# Sheet1.net
KiCad netlist of a schematic drawn in Altium Designer
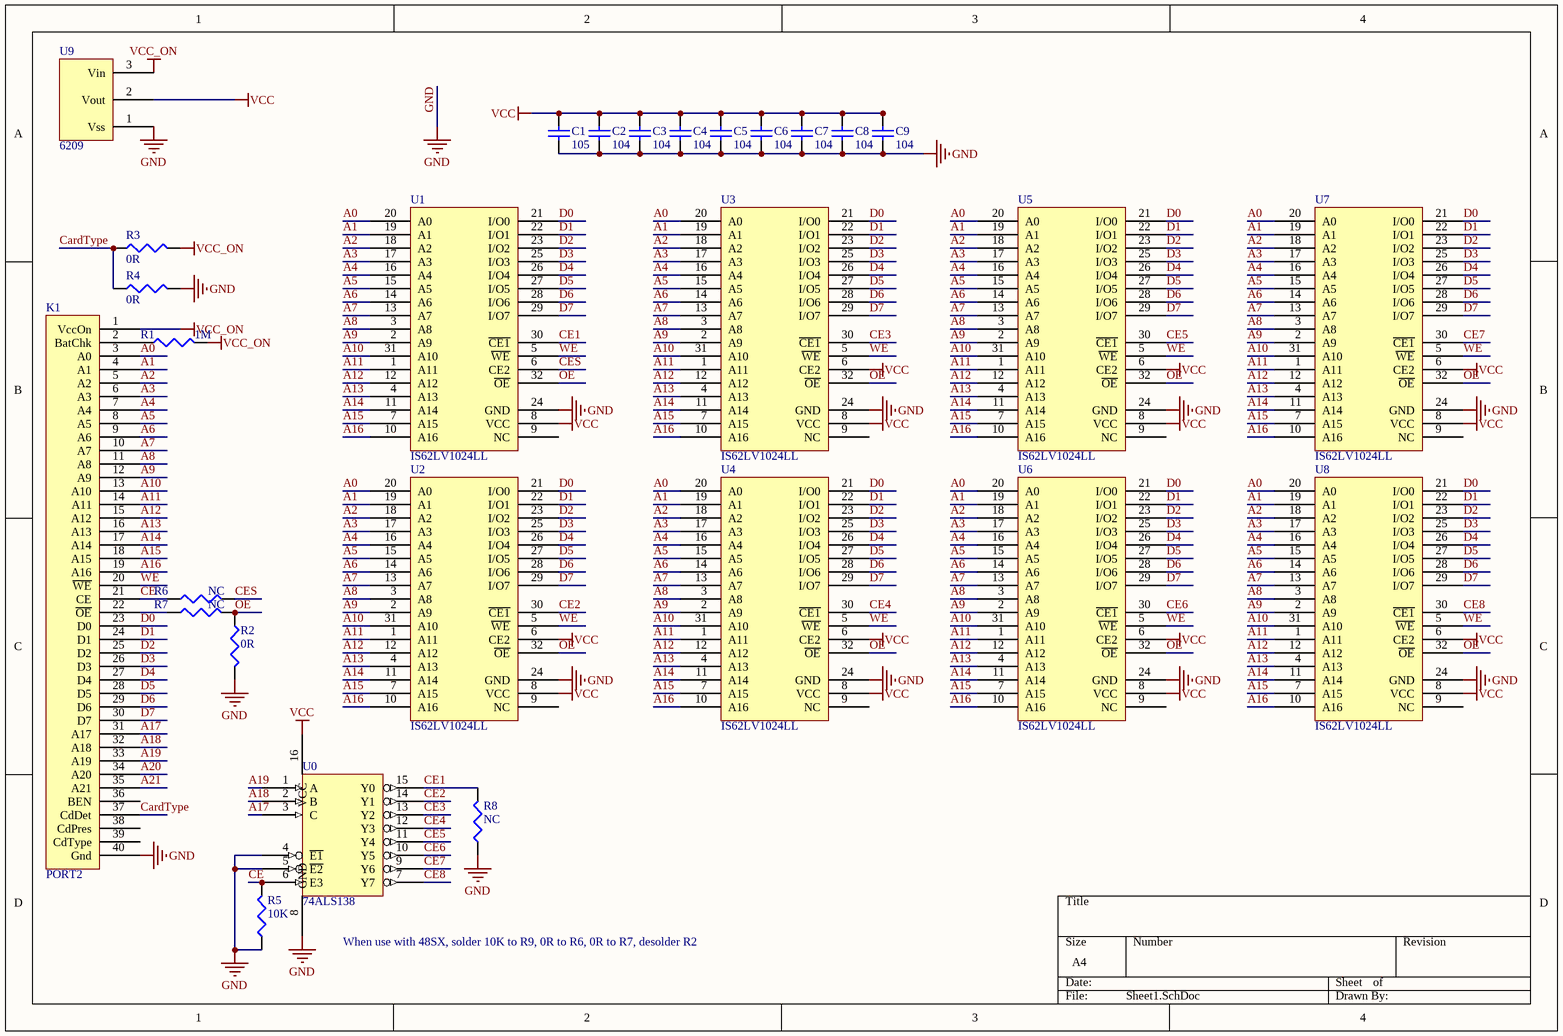
[diagram p0: Sheet1.SchDoc]

(export (version "E")
  (design (tool "Eeschema 10.0.6"))
  (components
    (comp (ref "C1")
      (value "105")
      (footprint "1608[0603]")
      (description "Capacitor (Semiconductor SIM Model)")
      (fields (field (name "PUBLISHER") "Altium Limited"))
      (libsource (lib "Miscellaneous Devices") (part "Cap Semi"))
    )
    (comp (ref "C2")
      (value "104")
      (footprint "1608[0603]")
      (description "Capacitor (Semiconductor SIM Model)")
      (fields (field (name "PUBLISHER") "Altium Limited"))
      (libsource (lib "Miscellaneous Devices") (part "Cap Semi"))
    )
    (comp (ref "C3")
      (value "104")
      (footprint "1608[0603]")
      (description "Capacitor (Semiconductor SIM Model)")
      (fields (field (name "PUBLISHER") "Altium Limited"))
      (libsource (lib "Miscellaneous Devices") (part "Cap Semi"))
    )
    (comp (ref "C4")
      (value "104")
      (footprint "1608[0603]")
      (description "Capacitor (Semiconductor SIM Model)")
      (fields (field (name "PUBLISHER") "Altium Limited"))
      (libsource (lib "Miscellaneous Devices") (part "Cap Semi"))
    )
    (comp (ref "C5")
      (value "104")
      (footprint "1608[0603]")
      (description "Capacitor (Semiconductor SIM Model)")
      (fields (field (name "PUBLISHER") "Altium Limited"))
      (libsource (lib "Miscellaneous Devices") (part "Cap Semi"))
    )
    (comp (ref "C6")
      (value "104")
      (footprint "1608[0603]")
      (description "Capacitor (Semiconductor SIM Model)")
      (fields (field (name "PUBLISHER") "Altium Limited"))
      (libsource (lib "Miscellaneous Devices") (part "Cap Semi"))
    )
    (comp (ref "C7")
      (value "104")
      (footprint "1608[0603]")
      (description "Capacitor (Semiconductor SIM Model)")
      (fields (field (name "PUBLISHER") "Altium Limited"))
      (libsource (lib "Miscellaneous Devices") (part "Cap Semi"))
    )
    (comp (ref "C8")
      (value "104")
      (footprint "1608[0603]")
      (description "Capacitor (Semiconductor SIM Model)")
      (fields (field (name "PUBLISHER") "Altium Limited"))
      (libsource (lib "Miscellaneous Devices") (part "Cap Semi"))
    )
    (comp (ref "C9")
      (value "104")
      (footprint "1608[0603]")
      (description "Capacitor (Semiconductor SIM Model)")
      (fields (field (name "PUBLISHER") "Altium Limited"))
      (libsource (lib "Miscellaneous Devices") (part "Cap Semi"))
    )
    (comp (ref "K1") (value "PORT2") (footprint "SOP80") (libsource (lib "Schlib1") (part "PORT2")))
    (comp (ref "R1")
      (value "1M")
      (footprint "J1-0603")
      (description "Resistor")
      (fields (field (name "PUBLISHER") "Altium Limited"))
      (libsource (lib "Miscellaneous Devices") (part "Res3"))
    )
    (comp (ref "R2")
      (value "0R")
      (footprint "J1-0603")
      (description "Resistor")
      (fields (field (name "PUBLISHER") "Altium Limited"))
      (libsource (lib "Miscellaneous Devices") (part "Res3"))
    )
    (comp (ref "R3")
      (value "0R")
      (footprint "J1-0603")
      (description "Resistor")
      (fields (field (name "PUBLISHER") "Altium Limited"))
      (libsource (lib "Miscellaneous Devices") (part "Res3"))
    )
    (comp (ref "R4")
      (value "0R")
      (footprint "J1-0603")
      (description "Resistor")
      (fields (field (name "PUBLISHER") "Altium Limited"))
      (libsource (lib "Miscellaneous Devices") (part "Res3"))
    )
    (comp (ref "R5")
      (value "10K")
      (footprint "J1-0603")
      (description "Resistor")
      (fields (field (name "PUBLISHER") "Altium Limited"))
      (libsource (lib "Miscellaneous Devices") (part "Res3"))
    )
    (comp (ref "R6")
      (value "NC")
      (footprint "J1-0603")
      (description "Resistor")
      (fields (field (name "PUBLISHER") "Altium Limited"))
      (libsource (lib "Miscellaneous Devices") (part "Res3"))
    )
    (comp (ref "R7")
      (value "NC")
      (footprint "J1-0603")
      (description "Resistor")
      (fields (field (name "PUBLISHER") "Altium Limited"))
      (libsource (lib "Miscellaneous Devices") (part "Res3"))
    )
    (comp (ref "R8")
      (value "NC")
      (footprint "J1-0603")
      (description "Resistor")
      (fields (field (name "PUBLISHER") "Altium Limited"))
      (libsource (lib "Miscellaneous Devices") (part "Res3"))
    )
    (comp (ref "U0") (value "74ALS138") (footprint "SO-16") (libsource (lib "TTL74系列IC") (part "74ALS138")))
    (comp (ref "U1")
      (value "IS62LV1024LL")
      (footprint "TSOP32")
      (libsource (lib "Schlib1") (part "IS62LV1024LL"))
    )
    (comp (ref "U2")
      (value "IS62LV1024LL")
      (footprint "TSOP32")
      (libsource (lib "Schlib1") (part "IS62LV1024LL"))
    )
    (comp (ref "U3")
      (value "IS62LV1024LL")
      (footprint "TSOP32")
      (libsource (lib "Schlib1") (part "IS62LV1024LL"))
    )
    (comp (ref "U4")
      (value "IS62LV1024LL")
      (footprint "TSOP32")
      (libsource (lib "Schlib1") (part "IS62LV1024LL"))
    )
    (comp (ref "U5")
      (value "IS62LV1024LL")
      (footprint "TSOP32")
      (libsource (lib "Schlib1") (part "IS62LV1024LL"))
    )
    (comp (ref "U6")
      (value "IS62LV1024LL")
      (footprint "TSOP32")
      (libsource (lib "Schlib1") (part "IS62LV1024LL"))
    )
    (comp (ref "U7")
      (value "IS62LV1024LL")
      (footprint "TSOP32")
      (libsource (lib "Schlib1") (part "IS62LV1024LL"))
    )
    (comp (ref "U8")
      (value "IS62LV1024LL")
      (footprint "TSOP32")
      (libsource (lib "Schlib1") (part "IS62LV1024LL"))
    )
    (comp (ref "U9") (value "6209") (footprint "SOT-23") (libsource (lib "Schlib1") (part "6209")))
  )
  (nets
    (net (code "1") (name "/A0") (class "Default")
      (node (ref "K1") (pin "3") (pinfunction "A0_3") (pintype "passive"))
      (node (ref "U1") (pin "20") (pinfunction "A0_20") (pintype "passive"))
      (node (ref "U2") (pin "20") (pinfunction "A0_20") (pintype "passive"))
      (node (ref "U3") (pin "20") (pinfunction "A0_20") (pintype "passive"))
      (node (ref "U4") (pin "20") (pinfunction "A0_20") (pintype "passive"))
      (node (ref "U5") (pin "20") (pinfunction "A0_20") (pintype "passive"))
      (node (ref "U6") (pin "20") (pinfunction "A0_20") (pintype "passive"))
      (node (ref "U7") (pin "20") (pinfunction "A0_20") (pintype "passive"))
      (node (ref "U8") (pin "20") (pinfunction "A0_20") (pintype "passive"))
    )
    (net (code "2") (name "/A1") (class "Default")
      (node (ref "K1") (pin "4") (pinfunction "A1_4") (pintype "passive"))
      (node (ref "U1") (pin "19") (pinfunction "A1_19") (pintype "passive"))
      (node (ref "U2") (pin "19") (pinfunction "A1_19") (pintype "passive"))
      (node (ref "U3") (pin "19") (pinfunction "A1_19") (pintype "passive"))
      (node (ref "U4") (pin "19") (pinfunction "A1_19") (pintype "passive"))
      (node (ref "U5") (pin "19") (pinfunction "A1_19") (pintype "passive"))
      (node (ref "U6") (pin "19") (pinfunction "A1_19") (pintype "passive"))
      (node (ref "U7") (pin "19") (pinfunction "A1_19") (pintype "passive"))
      (node (ref "U8") (pin "19") (pinfunction "A1_19") (pintype "passive"))
    )
    (net (code "3") (name "/A2") (class "Default")
      (node (ref "K1") (pin "5") (pinfunction "A2_5") (pintype "passive"))
      (node (ref "U1") (pin "18") (pinfunction "A2_18") (pintype "passive"))
      (node (ref "U2") (pin "18") (pinfunction "A2_18") (pintype "passive"))
      (node (ref "U3") (pin "18") (pinfunction "A2_18") (pintype "passive"))
      (node (ref "U4") (pin "18") (pinfunction "A2_18") (pintype "passive"))
      (node (ref "U5") (pin "18") (pinfunction "A2_18") (pintype "passive"))
      (node (ref "U6") (pin "18") (pinfunction "A2_18") (pintype "passive"))
      (node (ref "U7") (pin "18") (pinfunction "A2_18") (pintype "passive"))
      (node (ref "U8") (pin "18") (pinfunction "A2_18") (pintype "passive"))
    )
    (net (code "4") (name "/A3") (class "Default")
      (node (ref "K1") (pin "6") (pinfunction "A3_6") (pintype "passive"))
      (node (ref "U1") (pin "17") (pinfunction "A3_17") (pintype "passive"))
      (node (ref "U2") (pin "17") (pinfunction "A3_17") (pintype "passive"))
      (node (ref "U3") (pin "17") (pinfunction "A3_17") (pintype "passive"))
      (node (ref "U4") (pin "17") (pinfunction "A3_17") (pintype "passive"))
      (node (ref "U5") (pin "17") (pinfunction "A3_17") (pintype "passive"))
      (node (ref "U6") (pin "17") (pinfunction "A3_17") (pintype "passive"))
      (node (ref "U7") (pin "17") (pinfunction "A3_17") (pintype "passive"))
      (node (ref "U8") (pin "17") (pinfunction "A3_17") (pintype "passive"))
    )
    (net (code "5") (name "/A4") (class "Default")
      (node (ref "K1") (pin "7") (pinfunction "A4_7") (pintype "passive"))
      (node (ref "U1") (pin "16") (pinfunction "A4_16") (pintype "passive"))
      (node (ref "U2") (pin "16") (pinfunction "A4_16") (pintype "passive"))
      (node (ref "U3") (pin "16") (pinfunction "A4_16") (pintype "passive"))
      (node (ref "U4") (pin "16") (pinfunction "A4_16") (pintype "passive"))
      (node (ref "U5") (pin "16") (pinfunction "A4_16") (pintype "passive"))
      (node (ref "U6") (pin "16") (pinfunction "A4_16") (pintype "passive"))
      (node (ref "U7") (pin "16") (pinfunction "A4_16") (pintype "passive"))
      (node (ref "U8") (pin "16") (pinfunction "A4_16") (pintype "passive"))
    )
    (net (code "6") (name "/A5") (class "Default")
      (node (ref "K1") (pin "8") (pinfunction "A5_8") (pintype "passive"))
      (node (ref "U1") (pin "15") (pinfunction "A5_15") (pintype "passive"))
      (node (ref "U2") (pin "15") (pinfunction "A5_15") (pintype "passive"))
      (node (ref "U3") (pin "15") (pinfunction "A5_15") (pintype "passive"))
      (node (ref "U4") (pin "15") (pinfunction "A5_15") (pintype "passive"))
      (node (ref "U5") (pin "15") (pinfunction "A5_15") (pintype "passive"))
      (node (ref "U6") (pin "15") (pinfunction "A5_15") (pintype "passive"))
      (node (ref "U7") (pin "15") (pinfunction "A5_15") (pintype "passive"))
      (node (ref "U8") (pin "15") (pinfunction "A5_15") (pintype "passive"))
    )
    (net (code "7") (name "/A6") (class "Default")
      (node (ref "K1") (pin "9") (pinfunction "A6_9") (pintype "passive"))
      (node (ref "U1") (pin "14") (pinfunction "A6_14") (pintype "passive"))
      (node (ref "U2") (pin "14") (pinfunction "A6_14") (pintype "passive"))
      (node (ref "U3") (pin "14") (pinfunction "A6_14") (pintype "passive"))
      (node (ref "U4") (pin "14") (pinfunction "A6_14") (pintype "passive"))
      (node (ref "U5") (pin "14") (pinfunction "A6_14") (pintype "passive"))
      (node (ref "U6") (pin "14") (pinfunction "A6_14") (pintype "passive"))
      (node (ref "U7") (pin "14") (pinfunction "A6_14") (pintype "passive"))
      (node (ref "U8") (pin "14") (pinfunction "A6_14") (pintype "passive"))
    )
    (net (code "8") (name "/A7") (class "Default")
      (node (ref "K1") (pin "10") (pinfunction "A7_10") (pintype "passive"))
      (node (ref "U1") (pin "13") (pinfunction "A7_13") (pintype "passive"))
      (node (ref "U2") (pin "13") (pinfunction "A7_13") (pintype "passive"))
      (node (ref "U3") (pin "13") (pinfunction "A7_13") (pintype "passive"))
      (node (ref "U4") (pin "13") (pinfunction "A7_13") (pintype "passive"))
      (node (ref "U5") (pin "13") (pinfunction "A7_13") (pintype "passive"))
      (node (ref "U6") (pin "13") (pinfunction "A7_13") (pintype "passive"))
      (node (ref "U7") (pin "13") (pinfunction "A7_13") (pintype "passive"))
      (node (ref "U8") (pin "13") (pinfunction "A7_13") (pintype "passive"))
    )
    (net (code "9") (name "/A8") (class "Default")
      (node (ref "K1") (pin "11") (pinfunction "A8_11") (pintype "passive"))
      (node (ref "U1") (pin "3") (pinfunction "A8_3") (pintype "passive"))
      (node (ref "U2") (pin "3") (pinfunction "A8_3") (pintype "passive"))
      (node (ref "U3") (pin "3") (pinfunction "A8_3") (pintype "passive"))
      (node (ref "U4") (pin "3") (pinfunction "A8_3") (pintype "passive"))
      (node (ref "U5") (pin "3") (pinfunction "A8_3") (pintype "passive"))
      (node (ref "U6") (pin "3") (pinfunction "A8_3") (pintype "passive"))
      (node (ref "U7") (pin "3") (pinfunction "A8_3") (pintype "passive"))
      (node (ref "U8") (pin "3") (pinfunction "A8_3") (pintype "passive"))
    )
    (net (code "10") (name "/A9") (class "Default")
      (node (ref "K1") (pin "12") (pinfunction "A9_12") (pintype "passive"))
      (node (ref "U1") (pin "2") (pinfunction "A9_2") (pintype "passive"))
      (node (ref "U2") (pin "2") (pinfunction "A9_2") (pintype "passive"))
      (node (ref "U3") (pin "2") (pinfunction "A9_2") (pintype "passive"))
      (node (ref "U4") (pin "2") (pinfunction "A9_2") (pintype "passive"))
      (node (ref "U5") (pin "2") (pinfunction "A9_2") (pintype "passive"))
      (node (ref "U6") (pin "2") (pinfunction "A9_2") (pintype "passive"))
      (node (ref "U7") (pin "2") (pinfunction "A9_2") (pintype "passive"))
      (node (ref "U8") (pin "2") (pinfunction "A9_2") (pintype "passive"))
    )
    (net (code "11") (name "/A10") (class "Default")
      (node (ref "K1") (pin "13") (pinfunction "A10_13") (pintype "passive"))
      (node (ref "U1") (pin "31") (pinfunction "A10_31") (pintype "passive"))
      (node (ref "U2") (pin "31") (pinfunction "A10_31") (pintype "passive"))
      (node (ref "U3") (pin "31") (pinfunction "A10_31") (pintype "passive"))
      (node (ref "U4") (pin "31") (pinfunction "A10_31") (pintype "passive"))
      (node (ref "U5") (pin "31") (pinfunction "A10_31") (pintype "passive"))
      (node (ref "U6") (pin "31") (pinfunction "A10_31") (pintype "passive"))
      (node (ref "U7") (pin "31") (pinfunction "A10_31") (pintype "passive"))
      (node (ref "U8") (pin "31") (pinfunction "A10_31") (pintype "passive"))
    )
    (net (code "12") (name "/A11") (class "Default")
      (node (ref "K1") (pin "14") (pinfunction "A11_14") (pintype "passive"))
      (node (ref "U1") (pin "1") (pinfunction "A11_1") (pintype "passive"))
      (node (ref "U2") (pin "1") (pinfunction "A11_1") (pintype "passive"))
      (node (ref "U3") (pin "1") (pinfunction "A11_1") (pintype "passive"))
      (node (ref "U4") (pin "1") (pinfunction "A11_1") (pintype "passive"))
      (node (ref "U5") (pin "1") (pinfunction "A11_1") (pintype "passive"))
      (node (ref "U6") (pin "1") (pinfunction "A11_1") (pintype "passive"))
      (node (ref "U7") (pin "1") (pinfunction "A11_1") (pintype "passive"))
      (node (ref "U8") (pin "1") (pinfunction "A11_1") (pintype "passive"))
    )
    (net (code "13") (name "/A12") (class "Default")
      (node (ref "K1") (pin "15") (pinfunction "A12_15") (pintype "passive"))
      (node (ref "U1") (pin "12") (pinfunction "A12_12") (pintype "passive"))
      (node (ref "U2") (pin "12") (pinfunction "A12_12") (pintype "passive"))
      (node (ref "U3") (pin "12") (pinfunction "A12_12") (pintype "passive"))
      (node (ref "U4") (pin "12") (pinfunction "A12_12") (pintype "passive"))
      (node (ref "U5") (pin "12") (pinfunction "A12_12") (pintype "passive"))
      (node (ref "U6") (pin "12") (pinfunction "A12_12") (pintype "passive"))
      (node (ref "U7") (pin "12") (pinfunction "A12_12") (pintype "passive"))
      (node (ref "U8") (pin "12") (pinfunction "A12_12") (pintype "passive"))
    )
    (net (code "14") (name "/A13") (class "Default")
      (node (ref "K1") (pin "16") (pinfunction "A13_16") (pintype "passive"))
      (node (ref "U1") (pin "4") (pinfunction "A13_4") (pintype "passive"))
      (node (ref "U2") (pin "4") (pinfunction "A13_4") (pintype "passive"))
      (node (ref "U3") (pin "4") (pinfunction "A13_4") (pintype "passive"))
      (node (ref "U4") (pin "4") (pinfunction "A13_4") (pintype "passive"))
      (node (ref "U5") (pin "4") (pinfunction "A13_4") (pintype "passive"))
      (node (ref "U6") (pin "4") (pinfunction "A13_4") (pintype "passive"))
      (node (ref "U7") (pin "4") (pinfunction "A13_4") (pintype "passive"))
      (node (ref "U8") (pin "4") (pinfunction "A13_4") (pintype "passive"))
    )
    (net (code "15") (name "/A14") (class "Default")
      (node (ref "K1") (pin "17") (pinfunction "A14_17") (pintype "passive"))
      (node (ref "U1") (pin "11") (pinfunction "A14_11") (pintype "passive"))
      (node (ref "U2") (pin "11") (pinfunction "A14_11") (pintype "passive"))
      (node (ref "U3") (pin "11") (pinfunction "A14_11") (pintype "passive"))
      (node (ref "U4") (pin "11") (pinfunction "A14_11") (pintype "passive"))
      (node (ref "U5") (pin "11") (pinfunction "A14_11") (pintype "passive"))
      (node (ref "U6") (pin "11") (pinfunction "A14_11") (pintype "passive"))
      (node (ref "U7") (pin "11") (pinfunction "A14_11") (pintype "passive"))
      (node (ref "U8") (pin "11") (pinfunction "A14_11") (pintype "passive"))
    )
    (net (code "16") (name "/A15") (class "Default")
      (node (ref "K1") (pin "18") (pinfunction "A15_18") (pintype "passive"))
      (node (ref "U1") (pin "7") (pinfunction "A15_7") (pintype "passive"))
      (node (ref "U2") (pin "7") (pinfunction "A15_7") (pintype "passive"))
      (node (ref "U3") (pin "7") (pinfunction "A15_7") (pintype "passive"))
      (node (ref "U4") (pin "7") (pinfunction "A15_7") (pintype "passive"))
      (node (ref "U5") (pin "7") (pinfunction "A15_7") (pintype "passive"))
      (node (ref "U6") (pin "7") (pinfunction "A15_7") (pintype "passive"))
      (node (ref "U7") (pin "7") (pinfunction "A15_7") (pintype "passive"))
      (node (ref "U8") (pin "7") (pinfunction "A15_7") (pintype "passive"))
    )
    (net (code "17") (name "/A16") (class "Default")
      (node (ref "K1") (pin "19") (pinfunction "A16_19") (pintype "passive"))
      (node (ref "U1") (pin "10") (pinfunction "A16_10") (pintype "passive"))
      (node (ref "U2") (pin "10") (pinfunction "A16_10") (pintype "passive"))
      (node (ref "U3") (pin "10") (pinfunction "A16_10") (pintype "passive"))
      (node (ref "U4") (pin "10") (pinfunction "A16_10") (pintype "passive"))
      (node (ref "U5") (pin "10") (pinfunction "A16_10") (pintype "passive"))
      (node (ref "U6") (pin "10") (pinfunction "A16_10") (pintype "passive"))
      (node (ref "U7") (pin "10") (pinfunction "A16_10") (pintype "passive"))
      (node (ref "U8") (pin "10") (pinfunction "A16_10") (pintype "passive"))
    )
    (net (code "18") (name "/A17") (class "Default")
      (node (ref "K1") (pin "31") (pinfunction "A17_31") (pintype "passive"))
      (node (ref "U0") (pin "3") (pinfunction "C_3") (pintype "input"))
    )
    (net (code "19") (name "/A18") (class "Default")
      (node (ref "K1") (pin "32") (pinfunction "A18_32") (pintype "passive"))
      (node (ref "U0") (pin "2") (pinfunction "B_2") (pintype "input"))
    )
    (net (code "20") (name "/A19") (class "Default")
      (node (ref "K1") (pin "33") (pinfunction "A19_33") (pintype "passive"))
      (node (ref "U0") (pin "1") (pinfunction "A_1") (pintype "input"))
    )
    (net (code "21") (name "/A20") (class "Default")
      (node (ref "K1") (pin "34") (pinfunction "A20_34") (pintype "passive"))
    )
    (net (code "22") (name "/A21") (class "Default")
      (node (ref "K1") (pin "35") (pinfunction "A21_35") (pintype "passive"))
    )
    (net (code "23") (name "/CE") (class "Default")
      (node (ref "K1") (pin "21") (pinfunction "CE_21") (pintype "passive"))
      (node (ref "R5") (pin "2") (pinfunction "2_2") (pintype "passive"))
      (node (ref "R6") (pin "1") (pinfunction "1_1") (pintype "passive"))
      (node (ref "U0") (pin "6") (pinfunction "E3_6") (pintype "input"))
    )
    (net (code "24") (name "/CE1") (class "Default")
      (node (ref "R8") (pin "2") (pinfunction "2_2") (pintype "passive"))
      (node (ref "U0") (pin "15") (pinfunction "Y0_15") (pintype "output"))
      (node (ref "U1") (pin "30") (pinfunction "~{CE1}_30") (pintype "passive"))
    )
    (net (code "25") (name "/CE2") (class "Default")
      (node (ref "U0") (pin "14") (pinfunction "Y1_14") (pintype "output"))
      (node (ref "U2") (pin "30") (pinfunction "~{CE1}_30") (pintype "passive"))
    )
    (net (code "26") (name "/CE3") (class "Default")
      (node (ref "U0") (pin "13") (pinfunction "Y2_13") (pintype "output"))
      (node (ref "U3") (pin "30") (pinfunction "~{CE1}_30") (pintype "passive"))
    )
    (net (code "27") (name "/CE4") (class "Default")
      (node (ref "U0") (pin "12") (pinfunction "Y3_12") (pintype "output"))
      (node (ref "U4") (pin "30") (pinfunction "~{CE1}_30") (pintype "passive"))
    )
    (net (code "28") (name "/CE5") (class "Default")
      (node (ref "U0") (pin "11") (pinfunction "Y4_11") (pintype "output"))
      (node (ref "U5") (pin "30") (pinfunction "~{CE1}_30") (pintype "passive"))
    )
    (net (code "29") (name "/CE6") (class "Default")
      (node (ref "U0") (pin "10") (pinfunction "Y5_10") (pintype "output"))
      (node (ref "U6") (pin "30") (pinfunction "~{CE1}_30") (pintype "passive"))
    )
    (net (code "30") (name "/CE7") (class "Default")
      (node (ref "U0") (pin "9") (pinfunction "Y6_9") (pintype "output"))
      (node (ref "U7") (pin "30") (pinfunction "~{CE1}_30") (pintype "passive"))
    )
    (net (code "31") (name "/CE8") (class "Default")
      (node (ref "U0") (pin "7") (pinfunction "Y7_7") (pintype "output"))
      (node (ref "U8") (pin "30") (pinfunction "~{CE1}_30") (pintype "passive"))
    )
    (net (code "32") (name "/CES") (class "Default")
      (node (ref "R6") (pin "2") (pinfunction "2_2") (pintype "passive"))
      (node (ref "U1") (pin "6") (pinfunction "CE2_6") (pintype "passive"))
    )
    (net (code "33") (name "/CardType") (class "Default")
      (node (ref "K1") (pin "37") (pinfunction "CdDet_37") (pintype "passive"))
      (node (ref "R3") (pin "1") (pinfunction "1_1") (pintype "passive"))
      (node (ref "R4") (pin "1") (pinfunction "1_1") (pintype "passive"))
    )
    (net (code "34") (name "/D0") (class "Default")
      (node (ref "K1") (pin "23") (pinfunction "D0_23") (pintype "passive"))
      (node (ref "U1") (pin "21") (pinfunction "I/O0_21") (pintype "passive"))
      (node (ref "U2") (pin "21") (pinfunction "I/O0_21") (pintype "passive"))
      (node (ref "U3") (pin "21") (pinfunction "I/O0_21") (pintype "passive"))
      (node (ref "U4") (pin "21") (pinfunction "I/O0_21") (pintype "passive"))
      (node (ref "U5") (pin "21") (pinfunction "I/O0_21") (pintype "passive"))
      (node (ref "U6") (pin "21") (pinfunction "I/O0_21") (pintype "passive"))
      (node (ref "U7") (pin "21") (pinfunction "I/O0_21") (pintype "passive"))
      (node (ref "U8") (pin "21") (pinfunction "I/O0_21") (pintype "passive"))
    )
    (net (code "35") (name "/D1") (class "Default")
      (node (ref "K1") (pin "24") (pinfunction "D1_24") (pintype "passive"))
      (node (ref "U1") (pin "22") (pinfunction "I/O1_22") (pintype "passive"))
      (node (ref "U2") (pin "22") (pinfunction "I/O1_22") (pintype "passive"))
      (node (ref "U3") (pin "22") (pinfunction "I/O1_22") (pintype "passive"))
      (node (ref "U4") (pin "22") (pinfunction "I/O1_22") (pintype "passive"))
      (node (ref "U5") (pin "22") (pinfunction "I/O1_22") (pintype "passive"))
      (node (ref "U6") (pin "22") (pinfunction "I/O1_22") (pintype "passive"))
      (node (ref "U7") (pin "22") (pinfunction "I/O1_22") (pintype "passive"))
      (node (ref "U8") (pin "22") (pinfunction "I/O1_22") (pintype "passive"))
    )
    (net (code "36") (name "/D2") (class "Default")
      (node (ref "K1") (pin "25") (pinfunction "D2_25") (pintype "passive"))
      (node (ref "U1") (pin "23") (pinfunction "I/O2_23") (pintype "passive"))
      (node (ref "U2") (pin "23") (pinfunction "I/O2_23") (pintype "passive"))
      (node (ref "U3") (pin "23") (pinfunction "I/O2_23") (pintype "passive"))
      (node (ref "U4") (pin "23") (pinfunction "I/O2_23") (pintype "passive"))
      (node (ref "U5") (pin "23") (pinfunction "I/O2_23") (pintype "passive"))
      (node (ref "U6") (pin "23") (pinfunction "I/O2_23") (pintype "passive"))
      (node (ref "U7") (pin "23") (pinfunction "I/O2_23") (pintype "passive"))
      (node (ref "U8") (pin "23") (pinfunction "I/O2_23") (pintype "passive"))
    )
    (net (code "37") (name "/D3") (class "Default")
      (node (ref "K1") (pin "26") (pinfunction "D3_26") (pintype "passive"))
      (node (ref "U1") (pin "25") (pinfunction "I/O3_25") (pintype "passive"))
      (node (ref "U2") (pin "25") (pinfunction "I/O3_25") (pintype "passive"))
      (node (ref "U3") (pin "25") (pinfunction "I/O3_25") (pintype "passive"))
      (node (ref "U4") (pin "25") (pinfunction "I/O3_25") (pintype "passive"))
      (node (ref "U5") (pin "25") (pinfunction "I/O3_25") (pintype "passive"))
      (node (ref "U6") (pin "25") (pinfunction "I/O3_25") (pintype "passive"))
      (node (ref "U7") (pin "25") (pinfunction "I/O3_25") (pintype "passive"))
      (node (ref "U8") (pin "25") (pinfunction "I/O3_25") (pintype "passive"))
    )
    (net (code "38") (name "/D4") (class "Default")
      (node (ref "K1") (pin "27") (pinfunction "D4_27") (pintype "passive"))
      (node (ref "U1") (pin "26") (pinfunction "I/O4_26") (pintype "passive"))
      (node (ref "U2") (pin "26") (pinfunction "I/O4_26") (pintype "passive"))
      (node (ref "U3") (pin "26") (pinfunction "I/O4_26") (pintype "passive"))
      (node (ref "U4") (pin "26") (pinfunction "I/O4_26") (pintype "passive"))
      (node (ref "U5") (pin "26") (pinfunction "I/O4_26") (pintype "passive"))
      (node (ref "U6") (pin "26") (pinfunction "I/O4_26") (pintype "passive"))
      (node (ref "U7") (pin "26") (pinfunction "I/O4_26") (pintype "passive"))
      (node (ref "U8") (pin "26") (pinfunction "I/O4_26") (pintype "passive"))
    )
    (net (code "39") (name "/D5") (class "Default")
      (node (ref "K1") (pin "28") (pinfunction "D5_28") (pintype "passive"))
      (node (ref "U1") (pin "27") (pinfunction "I/O5_27") (pintype "passive"))
      (node (ref "U2") (pin "27") (pinfunction "I/O5_27") (pintype "passive"))
      (node (ref "U3") (pin "27") (pinfunction "I/O5_27") (pintype "passive"))
      (node (ref "U4") (pin "27") (pinfunction "I/O5_27") (pintype "passive"))
      (node (ref "U5") (pin "27") (pinfunction "I/O5_27") (pintype "passive"))
      (node (ref "U6") (pin "27") (pinfunction "I/O5_27") (pintype "passive"))
      (node (ref "U7") (pin "27") (pinfunction "I/O5_27") (pintype "passive"))
      (node (ref "U8") (pin "27") (pinfunction "I/O5_27") (pintype "passive"))
    )
    (net (code "40") (name "/D6") (class "Default")
      (node (ref "K1") (pin "29") (pinfunction "D6_29") (pintype "passive"))
      (node (ref "U1") (pin "28") (pinfunction "I/O6_28") (pintype "passive"))
      (node (ref "U2") (pin "28") (pinfunction "I/O6_28") (pintype "passive"))
      (node (ref "U3") (pin "28") (pinfunction "I/O6_28") (pintype "passive"))
      (node (ref "U4") (pin "28") (pinfunction "I/O6_28") (pintype "passive"))
      (node (ref "U5") (pin "28") (pinfunction "I/O6_28") (pintype "passive"))
      (node (ref "U6") (pin "28") (pinfunction "I/O6_28") (pintype "passive"))
      (node (ref "U7") (pin "28") (pinfunction "I/O6_28") (pintype "passive"))
      (node (ref "U8") (pin "28") (pinfunction "I/O6_28") (pintype "passive"))
    )
    (net (code "41") (name "/D7") (class "Default")
      (node (ref "K1") (pin "30") (pinfunction "D7_30") (pintype "passive"))
      (node (ref "U1") (pin "29") (pinfunction "I/O7_29") (pintype "passive"))
      (node (ref "U2") (pin "29") (pinfunction "I/O7_29") (pintype "passive"))
      (node (ref "U3") (pin "29") (pinfunction "I/O7_29") (pintype "passive"))
      (node (ref "U4") (pin "29") (pinfunction "I/O7_29") (pintype "passive"))
      (node (ref "U5") (pin "29") (pinfunction "I/O7_29") (pintype "passive"))
      (node (ref "U6") (pin "29") (pinfunction "I/O7_29") (pintype "passive"))
      (node (ref "U7") (pin "29") (pinfunction "I/O7_29") (pintype "passive"))
      (node (ref "U8") (pin "29") (pinfunction "I/O7_29") (pintype "passive"))
    )
    (net (code "42") (name "/OE") (class "Default")
      (node (ref "R2") (pin "1") (pinfunction "1_1") (pintype "passive"))
      (node (ref "R7") (pin "2") (pinfunction "2_2") (pintype "passive"))
      (node (ref "U1") (pin "32") (pinfunction "~{OE}_32") (pintype "passive"))
      (node (ref "U2") (pin "32") (pinfunction "~{OE}_32") (pintype "passive"))
      (node (ref "U3") (pin "32") (pinfunction "~{OE}_32") (pintype "passive"))
      (node (ref "U4") (pin "32") (pinfunction "~{OE}_32") (pintype "passive"))
      (node (ref "U5") (pin "32") (pinfunction "~{OE}_32") (pintype "passive"))
      (node (ref "U6") (pin "32") (pinfunction "~{OE}_32") (pintype "passive"))
      (node (ref "U7") (pin "32") (pinfunction "~{OE}_32") (pintype "passive"))
      (node (ref "U8") (pin "32") (pinfunction "~{OE}_32") (pintype "passive"))
    )
    (net (code "43") (name "/WE") (class "Default")
      (node (ref "K1") (pin "20") (pinfunction "~{WE}_20") (pintype "passive"))
      (node (ref "U1") (pin "5") (pinfunction "~{WE}_5") (pintype "passive"))
      (node (ref "U2") (pin "5") (pinfunction "~{WE}_5") (pintype "passive"))
      (node (ref "U3") (pin "5") (pinfunction "~{WE}_5") (pintype "passive"))
      (node (ref "U4") (pin "5") (pinfunction "~{WE}_5") (pintype "passive"))
      (node (ref "U5") (pin "5") (pinfunction "~{WE}_5") (pintype "passive"))
      (node (ref "U6") (pin "5") (pinfunction "~{WE}_5") (pintype "passive"))
      (node (ref "U7") (pin "5") (pinfunction "~{WE}_5") (pintype "passive"))
      (node (ref "U8") (pin "5") (pinfunction "~{WE}_5") (pintype "passive"))
    )
    (net (code "44") (name "GND") (class "Default")
      (node (ref "C1") (pin "1") (pinfunction "1_1") (pintype "passive"))
      (node (ref "C2") (pin "1") (pinfunction "1_1") (pintype "passive"))
      (node (ref "C3") (pin "1") (pinfunction "1_1") (pintype "passive"))
      (node (ref "C4") (pin "1") (pinfunction "1_1") (pintype "passive"))
      (node (ref "C5") (pin "1") (pinfunction "1_1") (pintype "passive"))
      (node (ref "C6") (pin "1") (pinfunction "1_1") (pintype "passive"))
      (node (ref "C7") (pin "1") (pinfunction "1_1") (pintype "passive"))
      (node (ref "C8") (pin "1") (pinfunction "1_1") (pintype "passive"))
      (node (ref "C9") (pin "1") (pinfunction "1_1") (pintype "passive"))
      (node (ref "K1") (pin "40") (pinfunction "Gnd_40") (pintype "passive"))
      (node (ref "R2") (pin "2") (pinfunction "2_2") (pintype "passive"))
      (node (ref "R4") (pin "2") (pinfunction "2_2") (pintype "passive"))
      (node (ref "R5") (pin "1") (pinfunction "1_1") (pintype "passive"))
      (node (ref "R8") (pin "1") (pinfunction "1_1") (pintype "passive"))
      (node (ref "U0") (pin "4") (pinfunction "~{E1}_4") (pintype "input"))
      (node (ref "U0") (pin "5") (pinfunction "~{E2}_5") (pintype "input"))
      (node (ref "U0") (pin "8") (pinfunction "GND_8") (pintype "power_in"))
      (node (ref "U1") (pin "24") (pinfunction "GND_24") (pintype "passive"))
      (node (ref "U2") (pin "24") (pinfunction "GND_24") (pintype "passive"))
      (node (ref "U3") (pin "24") (pinfunction "GND_24") (pintype "passive"))
      (node (ref "U4") (pin "24") (pinfunction "GND_24") (pintype "passive"))
      (node (ref "U5") (pin "24") (pinfunction "GND_24") (pintype "passive"))
      (node (ref "U6") (pin "24") (pinfunction "GND_24") (pintype "passive"))
      (node (ref "U7") (pin "24") (pinfunction "GND_24") (pintype "passive"))
      (node (ref "U8") (pin "24") (pinfunction "GND_24") (pintype "passive"))
      (node (ref "U9") (pin "1") (pinfunction "Vss_1") (pintype "passive"))
    )
    (net (code "45") (name "Net-(K1-BatChk)") (class "Default")
      (node (ref "K1") (pin "2") (pinfunction "BatChk_2") (pintype "passive"))
      (node (ref "R1") (pin "1") (pinfunction "1_1") (pintype "passive"))
    )
    (net (code "46") (name "Net-(K1-~{OE})") (class "Default")
      (node (ref "K1") (pin "22") (pinfunction "~{OE}_22") (pintype "passive"))
      (node (ref "R7") (pin "1") (pinfunction "1_1") (pintype "passive"))
    )
    (net (code "47") (name "VCC") (class "Default")
      (node (ref "C1") (pin "2") (pinfunction "2_2") (pintype "passive"))
      (node (ref "C2") (pin "2") (pinfunction "2_2") (pintype "passive"))
      (node (ref "C3") (pin "2") (pinfunction "2_2") (pintype "passive"))
      (node (ref "C4") (pin "2") (pinfunction "2_2") (pintype "passive"))
      (node (ref "C5") (pin "2") (pinfunction "2_2") (pintype "passive"))
      (node (ref "C6") (pin "2") (pinfunction "2_2") (pintype "passive"))
      (node (ref "C7") (pin "2") (pinfunction "2_2") (pintype "passive"))
      (node (ref "C8") (pin "2") (pinfunction "2_2") (pintype "passive"))
      (node (ref "C9") (pin "2") (pinfunction "2_2") (pintype "passive"))
      (node (ref "U0") (pin "16") (pinfunction "VCC_16") (pintype "power_in"))
      (node (ref "U1") (pin "8") (pinfunction "VCC_8") (pintype "passive"))
      (node (ref "U2") (pin "6") (pinfunction "CE2_6") (pintype "passive"))
      (node (ref "U2") (pin "8") (pinfunction "VCC_8") (pintype "passive"))
      (node (ref "U3") (pin "6") (pinfunction "CE2_6") (pintype "passive"))
      (node (ref "U3") (pin "8") (pinfunction "VCC_8") (pintype "passive"))
      (node (ref "U4") (pin "6") (pinfunction "CE2_6") (pintype "passive"))
      (node (ref "U4") (pin "8") (pinfunction "VCC_8") (pintype "passive"))
      (node (ref "U5") (pin "6") (pinfunction "CE2_6") (pintype "passive"))
      (node (ref "U5") (pin "8") (pinfunction "VCC_8") (pintype "passive"))
      (node (ref "U6") (pin "6") (pinfunction "CE2_6") (pintype "passive"))
      (node (ref "U6") (pin "8") (pinfunction "VCC_8") (pintype "passive"))
      (node (ref "U7") (pin "6") (pinfunction "CE2_6") (pintype "passive"))
      (node (ref "U7") (pin "8") (pinfunction "VCC_8") (pintype "passive"))
      (node (ref "U8") (pin "6") (pinfunction "CE2_6") (pintype "passive"))
      (node (ref "U8") (pin "8") (pinfunction "VCC_8") (pintype "passive"))
      (node (ref "U9") (pin "2") (pinfunction "Vout_2") (pintype "passive"))
    )
    (net (code "48") (name "VCC_ON") (class "Default")
      (node (ref "K1") (pin "1") (pinfunction "VccOn_1") (pintype "passive"))
      (node (ref "R1") (pin "2") (pinfunction "2_2") (pintype "passive"))
      (node (ref "R3") (pin "2") (pinfunction "2_2") (pintype "passive"))
      (node (ref "U9") (pin "3") (pinfunction "Vin_3") (pintype "passive"))
    )
    (net (code "49") (name "unconnected-(K1-BEN-Pad36)") (class "Default")
      (node (ref "K1") (pin "36") (pinfunction "BEN_36") (pintype "passive"))
    )
    (net (code "50") (name "unconnected-(K1-CdPres-Pad38)") (class "Default")
      (node (ref "K1") (pin "38") (pinfunction "CdPres_38") (pintype "passive"))
    )
    (net (code "51") (name "unconnected-(K1-CdType-Pad39)") (class "Default")
      (node (ref "K1") (pin "39") (pinfunction "CdType_39") (pintype "passive"))
    )
    (net (code "52") (name "unconnected-(U1-NC-Pad9)") (class "Default")
      (node (ref "U1") (pin "9") (pinfunction "NC_9") (pintype "passive"))
    )
    (net (code "53") (name "unconnected-(U2-NC-Pad9)") (class "Default")
      (node (ref "U2") (pin "9") (pinfunction "NC_9") (pintype "passive"))
    )
    (net (code "54") (name "unconnected-(U3-NC-Pad9)") (class "Default")
      (node (ref "U3") (pin "9") (pinfunction "NC_9") (pintype "passive"))
    )
    (net (code "55") (name "unconnected-(U4-NC-Pad9)") (class "Default")
      (node (ref "U4") (pin "9") (pinfunction "NC_9") (pintype "passive"))
    )
    (net (code "56") (name "unconnected-(U5-NC-Pad9)") (class "Default")
      (node (ref "U5") (pin "9") (pinfunction "NC_9") (pintype "passive"))
    )
    (net (code "57") (name "unconnected-(U6-NC-Pad9)") (class "Default")
      (node (ref "U6") (pin "9") (pinfunction "NC_9") (pintype "passive"))
    )
    (net (code "58") (name "unconnected-(U7-NC-Pad9)") (class "Default")
      (node (ref "U7") (pin "9") (pinfunction "NC_9") (pintype "passive"))
    )
    (net (code "59") (name "unconnected-(U8-NC-Pad9)") (class "Default")
      (node (ref "U8") (pin "9") (pinfunction "NC_9") (pintype "passive"))
    )
  )
)
